# Camera.net
KiCad netlist of a schematic drawn in Altium Designer
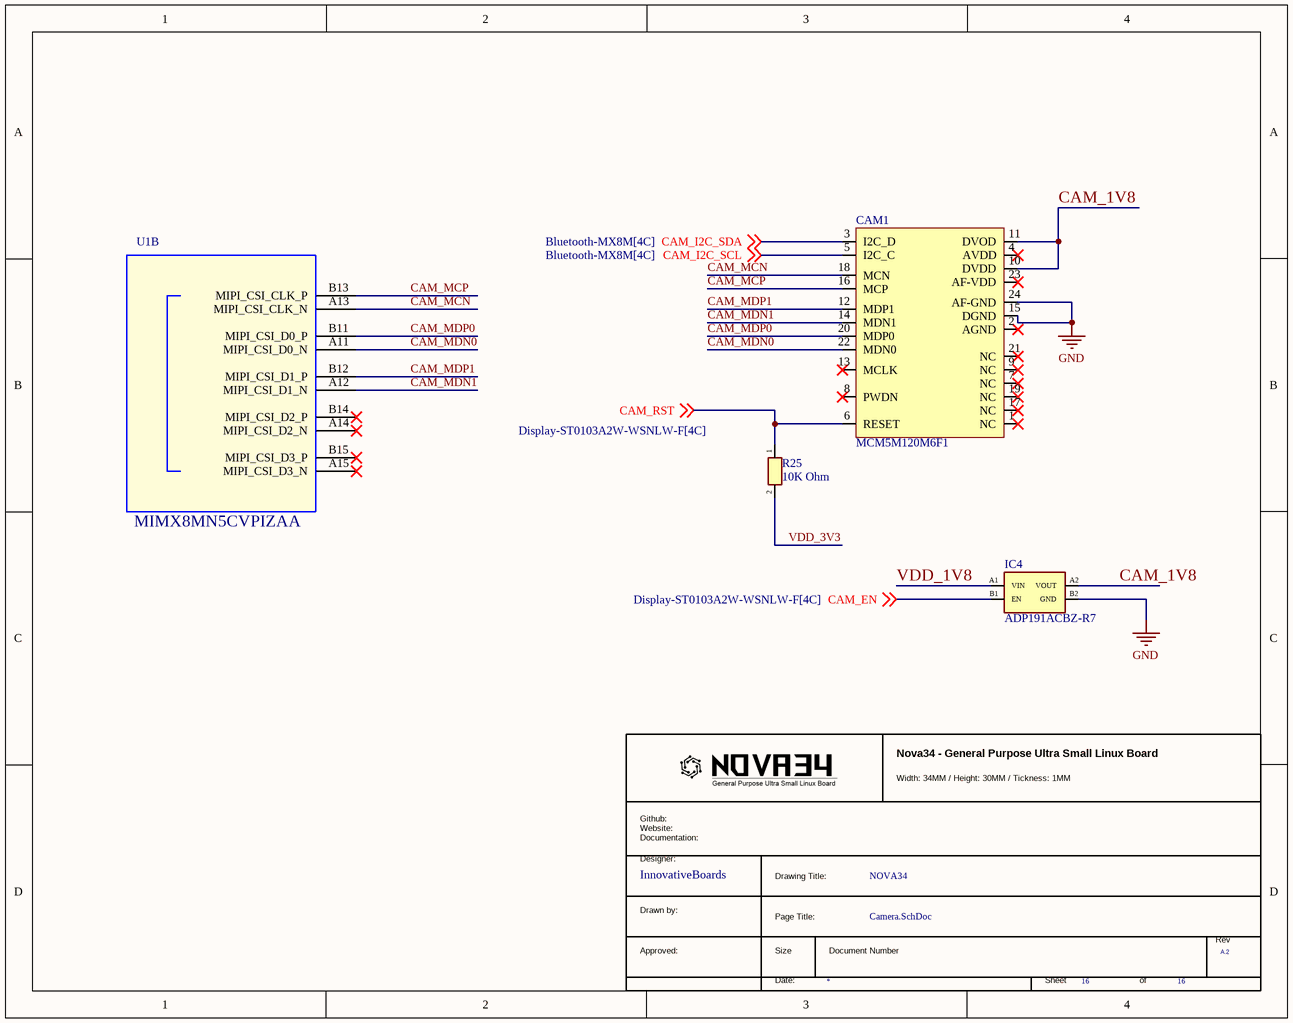
[diagram p0: Camera.SchDoc]

(export (version "E")
  (design (tool "Eeschema 10.0.6"))
  (components
    (comp (ref "*")
      (value "TitleBlock_MCPG")
      (fields (field (name "REVCODE") "A.2"))
      (libsource (lib "Nova_SCHLIB") (part "TitleBlock_MCPG"))
    )
    (comp (ref "CAM1")
      (value "MCM5M120M6F1")
      (footprint "MCM5M120M6F1")
      (description "MCM5M120M6F1 is a cost effective 5 Mega Pixel MIPI camera module with an M6 lens slot.")
      (libsource (lib "Nova_SCHLIB") (part "MCM5M120M6F1"))
    )
    (comp (ref "IC4")
      (value "ADP191ACBZ-R7")
      (footprint "BGA4C40P2X2_76X76X66")
      (description "Integrated Circuit")
      (fields (field (name "MOUSER PART NUMBER") "584-ADP191ACBZ-R7"))
      (libsource (lib "Nova_SCHLIB") (part "ADP191ACBZ-R7"))
    )
    (comp (ref "R25")
      (value "10K Ohm")
      (footprint "RESC1005X40N")
      (description "Resistor")
      (fields
        (field (name "MANUFACTURER_PART_NUMBER") "RC0402FR-0710KL")
        (field (name "MOUSER PART NUMBER") "603-RC0402FR-0710KL")
      )
      (libsource (lib "Nova_SCHLIB") (part "RC0402FR-0710KL"))
    )
    (comp (ref "U1")
      (value "MIMX8MN5CVPIZAA")
      (footprint "BGA306C50P21X21_1100X1100X101")
      (description "IC CPU QUAD CORTEX A53+M7 1.4GHZ -- BGA306")
      (libsource (lib "Nova_SCHLIB") (part "MIMX8MN"))
    )
  )
  (nets
    (net (code "1") (name "/CAM_1V8") (class "Default")
      (node (ref "CAM1") (pin "10") (pinfunction "DVDD_10") (pintype "passive"))
      (node (ref "CAM1") (pin "11") (pinfunction "DVOD_11") (pintype "passive"))
      (node (ref "IC4") (pin "A2") (pinfunction "VOUT_A2") (pintype "passive"))
    )
    (net (code "2") (name "/CAM_MCN") (class "Default")
      (node (ref "CAM1") (pin "18") (pinfunction "MCN_18") (pintype "passive"))
      (node (ref "U1") (pin "A13") (pinfunction "MIPI_CSI_CLK_N_A13") (pintype "passive"))
    )
    (net (code "3") (name "/CAM_MCP") (class "Default")
      (node (ref "CAM1") (pin "16") (pinfunction "MCP_16") (pintype "passive"))
      (node (ref "U1") (pin "B13") (pinfunction "MIPI_CSI_CLK_P_B13") (pintype "passive"))
    )
    (net (code "4") (name "/CAM_MDN0") (class "Default")
      (node (ref "CAM1") (pin "22") (pinfunction "MDN0_22") (pintype "passive"))
      (node (ref "U1") (pin "A11") (pinfunction "MIPI_CSI_D0_N_A11") (pintype "passive"))
    )
    (net (code "5") (name "/CAM_MDN1") (class "Default")
      (node (ref "CAM1") (pin "14") (pinfunction "MDN1_14") (pintype "passive"))
      (node (ref "U1") (pin "A12") (pinfunction "MIPI_CSI_D1_N_A12") (pintype "passive"))
    )
    (net (code "6") (name "/CAM_MDP0") (class "Default")
      (node (ref "CAM1") (pin "20") (pinfunction "MDP0_20") (pintype "passive"))
      (node (ref "U1") (pin "B11") (pinfunction "MIPI_CSI_D0_P_B11") (pintype "passive"))
    )
    (net (code "7") (name "/CAM_MDP1") (class "Default")
      (node (ref "CAM1") (pin "12") (pinfunction "MDP1_12") (pintype "passive"))
      (node (ref "U1") (pin "B12") (pinfunction "MIPI_CSI_D1_P_B12") (pintype "passive"))
    )
    (net (code "8") (name "/VDD_1V8") (class "Default")
      (node (ref "IC4") (pin "A1") (pinfunction "VIN_A1") (pintype "passive"))
    )
    (net (code "9") (name "/VDD_3V3") (class "Default")
      (node (ref "R25") (pin "2") (pinfunction "2_2") (pintype "passive"))
    )
    (net (code "10") (name "CAM_EN") (class "Default")
      (node (ref "IC4") (pin "B1") (pinfunction "EN_B1") (pintype "passive"))
    )
    (net (code "11") (name "CAM_I2C_SCL") (class "Default")
      (node (ref "CAM1") (pin "5") (pinfunction "I2C_C_5") (pintype "passive"))
    )
    (net (code "12") (name "CAM_I2C_SDA") (class "Default")
      (node (ref "CAM1") (pin "3") (pinfunction "I2C_D_3") (pintype "passive"))
    )
    (net (code "13") (name "CAM_RST") (class "Default")
      (node (ref "CAM1") (pin "6") (pinfunction "RESET_6") (pintype "passive"))
      (node (ref "R25") (pin "1") (pinfunction "1_1") (pintype "passive"))
    )
    (net (code "14") (name "GND") (class "Default")
      (node (ref "CAM1") (pin "15") (pinfunction "DGND_15") (pintype "passive"))
      (node (ref "CAM1") (pin "24") (pinfunction "AF-GND_24") (pintype "passive"))
      (node (ref "IC4") (pin "B2") (pinfunction "GND_B2") (pintype "passive"))
    )
    (net (code "15") (name "unconnected-(CAM1-AF-VDD-Pad23)") (class "Default")
      (node (ref "CAM1") (pin "23") (pinfunction "AF-VDD_23") (pintype "passive+no_connect"))
    )
    (net (code "16") (name "unconnected-(CAM1-AGND-Pad2)") (class "Default")
      (node (ref "CAM1") (pin "2") (pinfunction "AGND_2") (pintype "passive+no_connect"))
    )
    (net (code "17") (name "unconnected-(CAM1-AVDD-Pad4)") (class "Default")
      (node (ref "CAM1") (pin "4") (pinfunction "AVDD_4") (pintype "passive+no_connect"))
    )
    (net (code "18") (name "unconnected-(CAM1-MCLK-Pad13)") (class "Default")
      (node (ref "CAM1") (pin "13") (pinfunction "MCLK_13") (pintype "passive+no_connect"))
    )
    (net (code "19") (name "unconnected-(CAM1-NC-Pad1)") (class "Default")
      (node (ref "CAM1") (pin "1") (pinfunction "NC_1") (pintype "passive+no_connect"))
    )
    (net (code "20") (name "unconnected-(CAM1-NC-Pad7)") (class "Default")
      (node (ref "CAM1") (pin "7") (pinfunction "NC_7") (pintype "passive+no_connect"))
    )
    (net (code "21") (name "unconnected-(CAM1-NC-Pad9)") (class "Default")
      (node (ref "CAM1") (pin "9") (pinfunction "NC_9") (pintype "passive+no_connect"))
    )
    (net (code "22") (name "unconnected-(CAM1-NC-Pad17)") (class "Default")
      (node (ref "CAM1") (pin "17") (pinfunction "NC_17") (pintype "passive+no_connect"))
    )
    (net (code "23") (name "unconnected-(CAM1-NC-Pad19)") (class "Default")
      (node (ref "CAM1") (pin "19") (pinfunction "NC_19") (pintype "passive+no_connect"))
    )
    (net (code "24") (name "unconnected-(CAM1-NC-Pad21)") (class "Default")
      (node (ref "CAM1") (pin "21") (pinfunction "NC_21") (pintype "passive+no_connect"))
    )
    (net (code "25") (name "unconnected-(CAM1-PWDN-Pad8)") (class "Default")
      (node (ref "CAM1") (pin "8") (pinfunction "PWDN_8") (pintype "passive+no_connect"))
    )
    (net (code "26") (name "unconnected-(U1B-MIPI_CSI_D2_N-PadA14)") (class "Default")
      (node (ref "U1") (pin "A14") (pinfunction "MIPI_CSI_D2_N_A14") (pintype "passive+no_connect"))
    )
    (net (code "27") (name "unconnected-(U1B-MIPI_CSI_D2_P-PadB14)") (class "Default")
      (node (ref "U1") (pin "B14") (pinfunction "MIPI_CSI_D2_P_B14") (pintype "passive+no_connect"))
    )
    (net (code "28") (name "unconnected-(U1B-MIPI_CSI_D3_N-PadA15)") (class "Default")
      (node (ref "U1") (pin "A15") (pinfunction "MIPI_CSI_D3_N_A15") (pintype "passive+no_connect"))
    )
    (net (code "29") (name "unconnected-(U1B-MIPI_CSI_D3_P-PadB15)") (class "Default")
      (node (ref "U1") (pin "B15") (pinfunction "MIPI_CSI_D3_P_B15") (pintype "passive+no_connect"))
    )
  )
)
